# OPTIC.net
KiCad netlist of a schematic drawn in Altium Designer
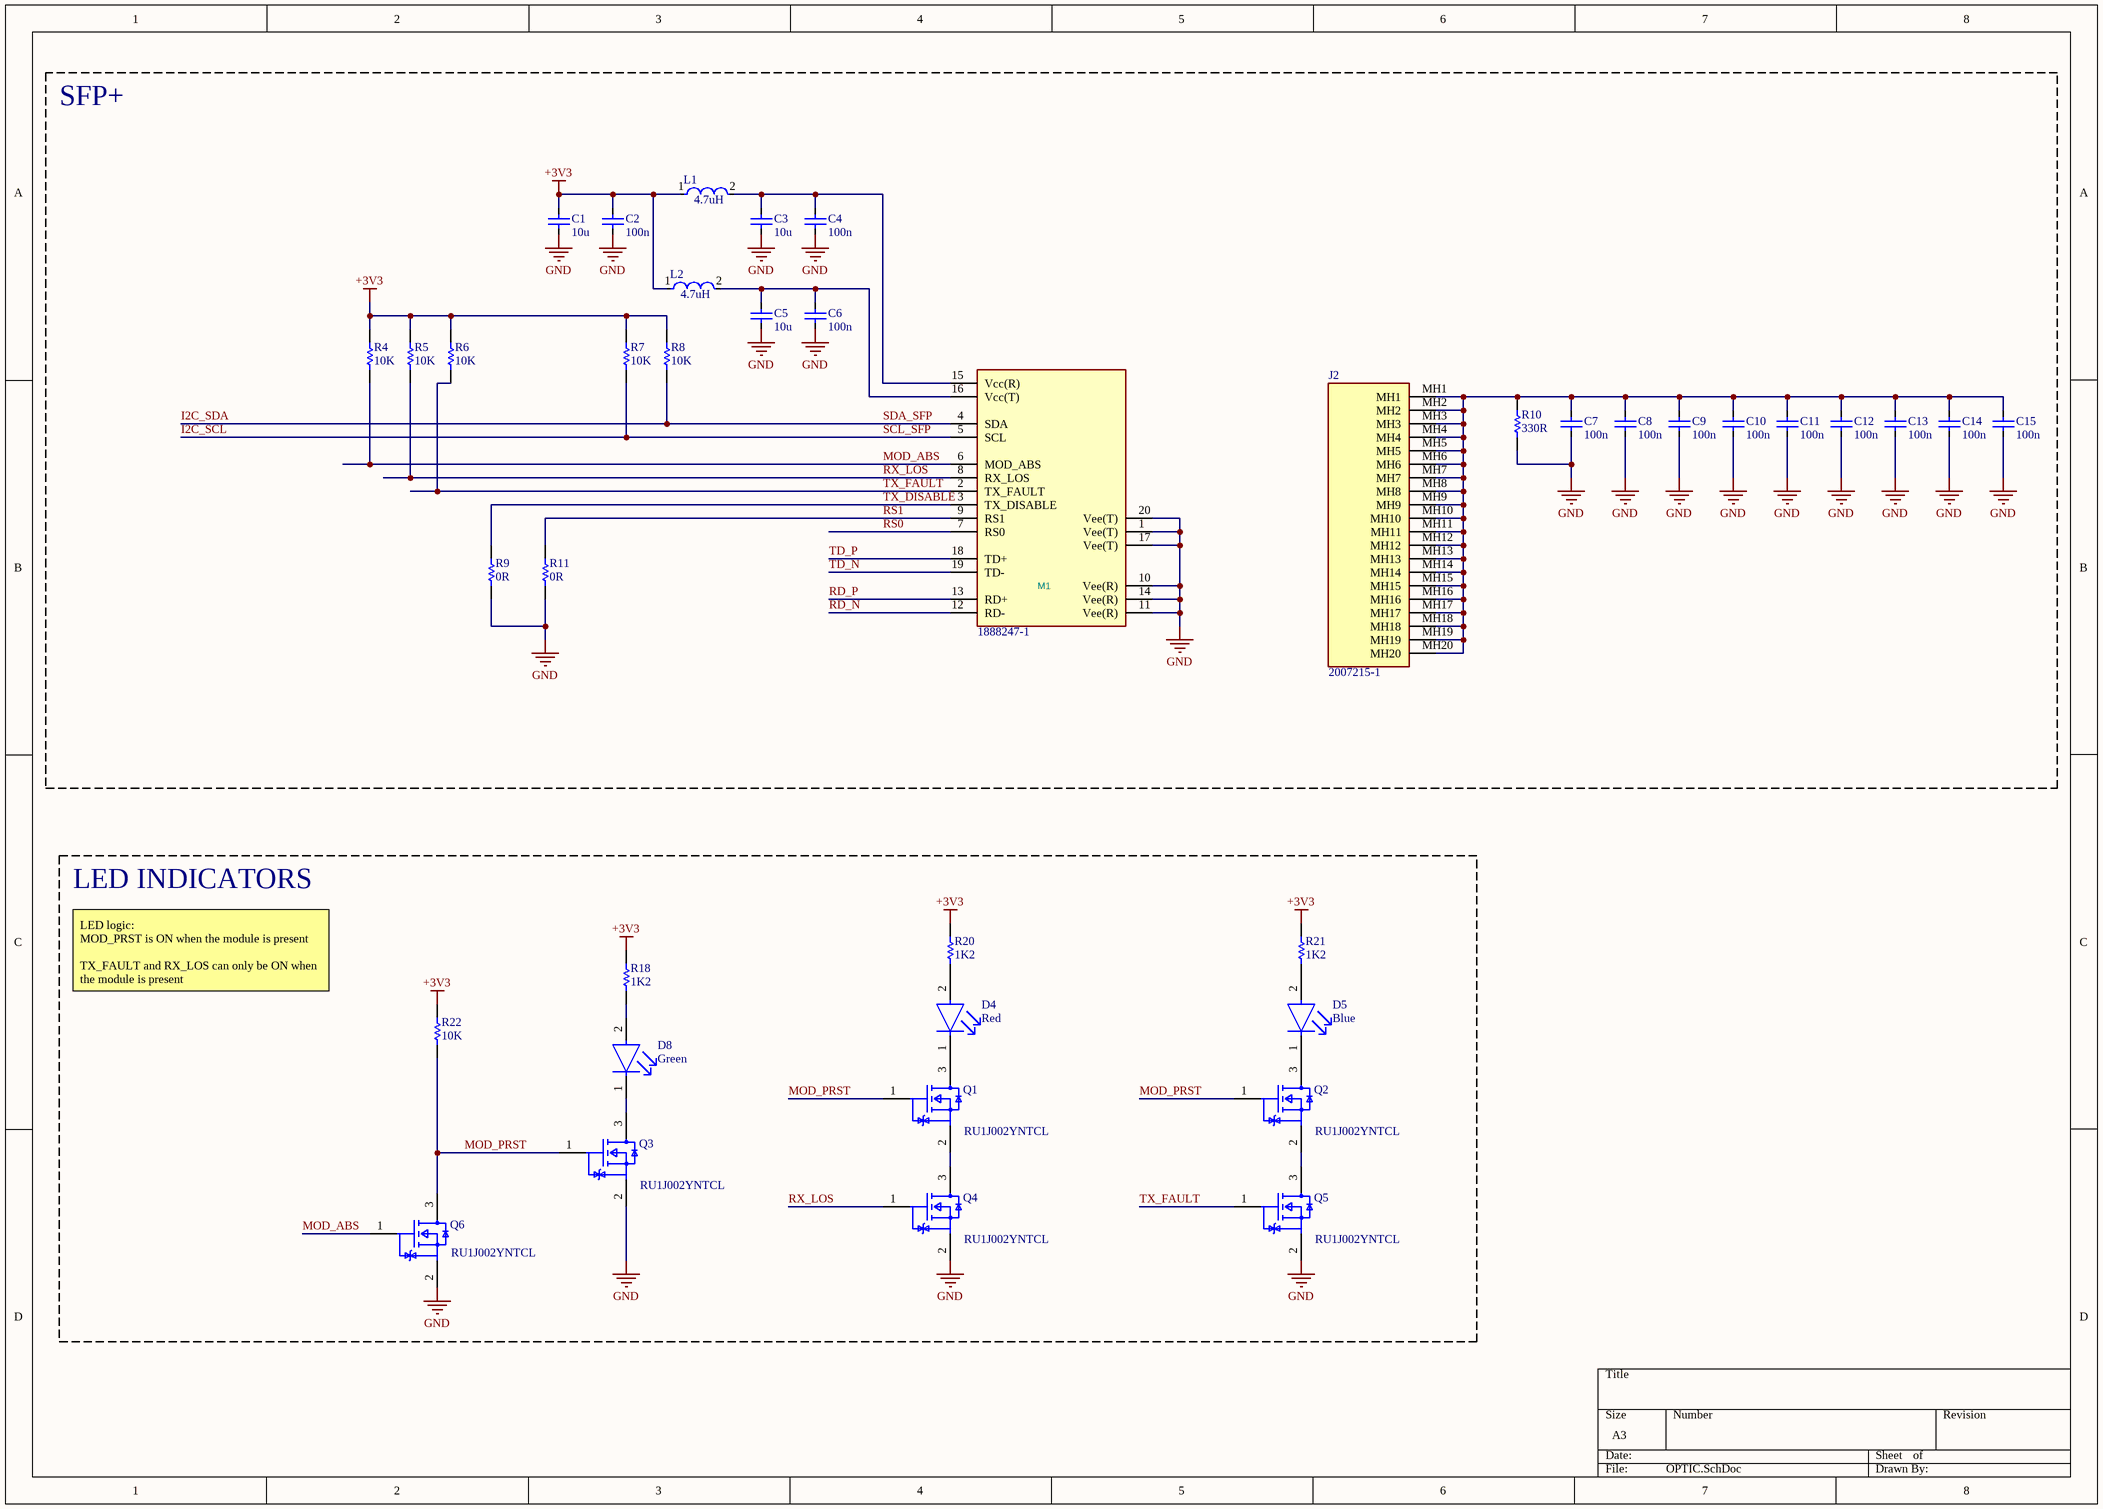
[diagram p0: OPTIC.SchDoc]

(export (version "E")
  (design (tool "Eeschema 10.0.6"))
  (components
    (comp (ref "C1")
      (value "10u")
      (footprint "FP-C1608-080-0_1-IPC_C")
      (description "MLCC 10μF ±10% 6.3V JB SMD 0603")
      (fields (field (name "TOLERANCE") "10%") (field (name "Comment") "C1608JB0J106K080AB"))
      (libsource (lib "Schlib1") (part "C1608JB0J106K080AB"))
    )
    (comp (ref "C2")
      (value "100n")
      (footprint "FP-C1005-050-0_05-IPC_C")
      (description "MLCC 100nF ±10% 50V X7R SMD 0402")
      (fields (field (name "VOLTAGE") "50V") (field (name "TOLERANCE") "10%"))
      (libsource (lib "Schlib1") (part "C1005X7R1H104K050BB"))
    )
    (comp (ref "C3")
      (value "10u")
      (footprint "FP-C1608-080-0_1-IPC_C")
      (description "MLCC 10μF ±10% 6.3V JB SMD 0603")
      (fields (field (name "TOLERANCE") "10%") (field (name "Comment") "C1608JB0J106K080AB"))
      (libsource (lib "Schlib1") (part "C1608JB0J106K080AB"))
    )
    (comp (ref "C4")
      (value "100n")
      (footprint "FP-C1005-050-0_05-IPC_C")
      (description "MLCC 100nF ±10% 50V X7R SMD 0402")
      (fields (field (name "VOLTAGE") "50V") (field (name "TOLERANCE") "10%"))
      (libsource (lib "Schlib1") (part "C1005X7R1H104K050BB"))
    )
    (comp (ref "C5")
      (value "10u")
      (footprint "FP-C1608-080-0_1-IPC_C")
      (description "MLCC 10μF ±10% 6.3V JB SMD 0603")
      (fields (field (name "TOLERANCE") "10%") (field (name "Comment") "C1608JB0J106K080AB"))
      (libsource (lib "Schlib1") (part "C1608JB0J106K080AB"))
    )
    (comp (ref "C6")
      (value "100n")
      (footprint "FP-C1005-050-0_05-IPC_C")
      (description "MLCC 100nF ±10% 50V X7R SMD 0402")
      (fields (field (name "VOLTAGE") "50V") (field (name "TOLERANCE") "10%"))
      (libsource (lib "Schlib1") (part "C1005X7R1H104K050BB"))
    )
    (comp (ref "C7")
      (value "100n")
      (footprint "FP-C1005-050-0_05-IPC_C")
      (description "MLCC 100nF ±10% 50V X7R SMD 0402")
      (fields (field (name "VOLTAGE") "50V") (field (name "TOLERANCE") "10%"))
      (libsource (lib "Schlib1") (part "C1005X7R1H104K050BB"))
    )
    (comp (ref "C8")
      (value "100n")
      (footprint "FP-C1005-050-0_05-IPC_C")
      (description "MLCC 100nF ±10% 50V X7R SMD 0402")
      (fields (field (name "VOLTAGE") "50V") (field (name "TOLERANCE") "10%"))
      (libsource (lib "Schlib1") (part "C1005X7R1H104K050BB"))
    )
    (comp (ref "C9")
      (value "100n")
      (footprint "FP-C1005-050-0_05-IPC_C")
      (description "MLCC 100nF ±10% 50V X7R SMD 0402")
      (fields (field (name "VOLTAGE") "50V") (field (name "TOLERANCE") "10%"))
      (libsource (lib "Schlib1") (part "C1005X7R1H104K050BB"))
    )
    (comp (ref "C10")
      (value "100n")
      (footprint "FP-C1005-050-0_05-IPC_C")
      (description "MLCC 100nF ±10% 50V X7R SMD 0402")
      (fields (field (name "VOLTAGE") "50V") (field (name "TOLERANCE") "10%"))
      (libsource (lib "Schlib1") (part "C1005X7R1H104K050BB"))
    )
    (comp (ref "C11")
      (value "100n")
      (footprint "FP-C1005-050-0_05-IPC_C")
      (description "MLCC 100nF ±10% 50V X7R SMD 0402")
      (fields (field (name "VOLTAGE") "50V") (field (name "TOLERANCE") "10%"))
      (libsource (lib "Schlib1") (part "C1005X7R1H104K050BB"))
    )
    (comp (ref "C12")
      (value "100n")
      (footprint "FP-C1005-050-0_05-IPC_C")
      (description "MLCC 100nF ±10% 50V X7R SMD 0402")
      (fields (field (name "VOLTAGE") "50V") (field (name "TOLERANCE") "10%"))
      (libsource (lib "Schlib1") (part "C1005X7R1H104K050BB"))
    )
    (comp (ref "C13")
      (value "100n")
      (footprint "FP-C1005-050-0_05-IPC_C")
      (description "MLCC 100nF ±10% 50V X7R SMD 0402")
      (fields (field (name "VOLTAGE") "50V") (field (name "TOLERANCE") "10%"))
      (libsource (lib "Schlib1") (part "C1005X7R1H104K050BB"))
    )
    (comp (ref "C14")
      (value "100n")
      (footprint "FP-C1005-050-0_05-IPC_C")
      (description "MLCC 100nF ±10% 50V X7R SMD 0402")
      (fields (field (name "VOLTAGE") "50V") (field (name "TOLERANCE") "10%"))
      (libsource (lib "Schlib1") (part "C1005X7R1H104K050BB"))
    )
    (comp (ref "C15")
      (value "100n")
      (footprint "FP-C1005-050-0_05-IPC_C")
      (description "MLCC 100nF ±10% 50V X7R SMD 0402")
      (fields (field (name "VOLTAGE") "50V") (field (name "TOLERANCE") "10%"))
      (libsource (lib "Schlib1") (part "C1005X7R1H104K050BB"))
    )
    (comp (ref "D4")
      (value "LTST-C191KRKT")
      (footprint "FP-LTST-C191KRKT-MFG")
      (fields (field (name "VOLTAGE") "2V") (field (name "COLOR") "Red"))
      (libsource (lib "Altium Content Vault") (part "8706943c75ba83719d021d2fdc84c58"))
    )
    (comp (ref "D5")
      (value "LTST-C191TBKT")
      (footprint "FP-LTST-C191TBKT-MFG")
      (description "LED BLUE CLEAR CHIP SMD")
      (fields (field (name "COLOR") "Blue"))
      (libsource (lib "Altium Content Vault") (part "8706943c75ba83719d021d2fdc84c58"))
    )
    (comp (ref "D8")
      (value "LTST-C191GKT")
      (footprint "FP-LTST-C191GKT-MFG")
      (description "LED GREEN CLEAR CHIP SMD")
      (fields (field (name "COLOR") "Green"))
      (libsource (lib "Altium Content Vault") (part "8706943c75ba83719d021d2fdc84c58"))
    )
    (comp (ref "J2")
      (value "2007215-1")
      (footprint "2007215-1")
      (description "Position SFP+ Cage Connector Press-Fit Through Hole")
      (libsource (lib "Schlib1") (part "2007215-1"))
    )
    (comp (ref "L1")
      (value "DFE252012P-4R7M=P2")
      (footprint "FP-DFE252012C-IPC_C")
      (description "Shielded Wirewound Inductor 4.7uH 20% 1400mA 0.2Ω 1008 (2520)")
      (fields (field (name "INDUCTANCE") "4.7uH") (field (name "TOLERANCE") "20%"))
      (libsource (lib "Altium Content Vault") (part "725321dda6339637d4d059423bc1c3c"))
    )
    (comp (ref "L2")
      (value "DFE252012P-4R7M=P2")
      (footprint "FP-DFE252012C-IPC_C")
      (description "Shielded Wirewound Inductor 4.7uH 20% 1400mA 0.2Ω 1008 (2520)")
      (fields (field (name "INDUCTANCE") "4.7uH") (field (name "TOLERANCE") "20%"))
      (libsource (lib "Altium Content Vault") (part "725321dda6339637d4d059423bc1c3c"))
    )
    (comp (ref "M1")
      (value "1888247-1")
      (footprint "1888247-1")
      (fields (field (name "MANUFACTURER") "TE Connectivity (TE") (field (name "AUTHOR") "Parsa Malekpor"))
      (libsource (lib "Schlib1") (part "1888247-1"))
    )
    (comp (ref "Q1")
      (value "RU1J002YNTCL")
      (footprint "FP-UMT3F-MFG")
      (description "MOSFET N-CH 50V 0.2A UMT3F")
      (fields
        (field (name "MANUFACTURER") "Rohm")
        (field (name "OCTOPART") "https://octopart.com/ru1j002yntcl-rohm-47197697")
      )
      (libsource (lib "Schlib1") (part "RU1J002YNTCL"))
    )
    (comp (ref "Q2")
      (value "RU1J002YNTCL")
      (footprint "FP-UMT3F-MFG")
      (description "MOSFET N-CH 50V 0.2A UMT3F")
      (fields
        (field (name "MANUFACTURER") "Rohm")
        (field (name "OCTOPART") "https://octopart.com/ru1j002yntcl-rohm-47197697")
      )
      (libsource (lib "Schlib1") (part "RU1J002YNTCL"))
    )
    (comp (ref "Q3")
      (value "RU1J002YNTCL")
      (footprint "FP-UMT3F-MFG")
      (description "MOSFET N-CH 50V 0.2A UMT3F")
      (fields
        (field (name "MANUFACTURER") "Rohm")
        (field (name "OCTOPART") "https://octopart.com/ru1j002yntcl-rohm-47197697")
      )
      (libsource (lib "Schlib1") (part "RU1J002YNTCL"))
    )
    (comp (ref "Q4")
      (value "RU1J002YNTCL")
      (footprint "FP-UMT3F-MFG")
      (description "MOSFET N-CH 50V 0.2A UMT3F")
      (fields
        (field (name "MANUFACTURER") "Rohm")
        (field (name "OCTOPART") "https://octopart.com/ru1j002yntcl-rohm-47197697")
      )
      (libsource (lib "Schlib1") (part "RU1J002YNTCL"))
    )
    (comp (ref "Q5")
      (value "RU1J002YNTCL")
      (footprint "FP-UMT3F-MFG")
      (description "MOSFET N-CH 50V 0.2A UMT3F")
      (fields
        (field (name "MANUFACTURER") "Rohm")
        (field (name "OCTOPART") "https://octopart.com/ru1j002yntcl-rohm-47197697")
      )
      (libsource (lib "Schlib1") (part "RU1J002YNTCL"))
    )
    (comp (ref "Q6")
      (value "RU1J002YNTCL")
      (footprint "FP-UMT3F-MFG")
      (description "MOSFET N-CH 50V 0.2A UMT3F")
      (fields
        (field (name "MANUFACTURER") "Rohm")
        (field (name "OCTOPART") "https://octopart.com/ru1j002yntcl-rohm-47197697")
      )
      (libsource (lib "Schlib1") (part "RU1J002YNTCL"))
    )
    (comp (ref "R4")
      (value "10K")
      (footprint "RESC1005X40X25LL05T10")
      (fields (field (name "PART NUMBER") "RC0402FR-0710KL") (field (name "MANUFACTURER") "Yageo / Phycomp"))
      (libsource (lib "Altium Content Vault") (part "RES"))
    )
    (comp (ref "R5")
      (value "10K")
      (footprint "RESC1005X40X25LL05T10")
      (fields (field (name "PART NUMBER") "RC0402FR-0710KL") (field (name "MANUFACTURER") "Yageo / Phycomp"))
      (libsource (lib "Altium Content Vault") (part "RES"))
    )
    (comp (ref "R6")
      (value "10K")
      (footprint "RESC1005X40X25LL05T10")
      (fields (field (name "PART NUMBER") "RC0402FR-0710KL") (field (name "MANUFACTURER") "Yageo / Phycomp"))
      (libsource (lib "Altium Content Vault") (part "RES"))
    )
    (comp (ref "R7")
      (value "10K")
      (footprint "RESC1005X40X25LL05T10")
      (fields (field (name "PART NUMBER") "RC0402FR-0710KL") (field (name "MANUFACTURER") "Yageo / Phycomp"))
      (libsource (lib "Altium Content Vault") (part "RES"))
    )
    (comp (ref "R8")
      (value "10K")
      (footprint "RESC1005X40X25LL05T10")
      (fields (field (name "PART NUMBER") "RC0402FR-0710KL") (field (name "MANUFACTURER") "Yageo / Phycomp"))
      (libsource (lib "Altium Content Vault") (part "RES"))
    )
    (comp (ref "R9")
      (value "0R")
      (footprint "RESC1005X40X25LL05T10")
      (fields (field (name "PART NUMBER") "RC0402FR-070RL") (field (name "MANUFACTURER") "Yageo / Phycomp"))
      (libsource (lib "Altium Content Vault") (part "RES"))
    )
    (comp (ref "R10")
      (value "330R")
      (footprint "RESC1005X40X25LL05T10")
      (fields (field (name "PART NUMBER") "RC0402FR-07330RL") (field (name "MANUFACTURER") "Yageo / Phycomp"))
      (libsource (lib "Altium Content Vault") (part "RES"))
    )
    (comp (ref "R11")
      (value "0R")
      (footprint "RESC1005X40X25LL05T10")
      (fields (field (name "PART NUMBER") "RC0402FR-070RL") (field (name "MANUFACTURER") "Yageo / Phycomp"))
      (libsource (lib "Altium Content Vault") (part "RES"))
    )
    (comp (ref "R18")
      (value "1K2")
      (footprint "RESC1005X40X25ML05T10")
      (fields (field (name "PART NUMBER") "RC0402FR-071K2L") (field (name "MANUFACTURER") "Yageo / Phycomp"))
      (libsource (lib "Altium Content Vault") (part "RES"))
    )
    (comp (ref "R20")
      (value "1K2")
      (footprint "RESC1005X40X25ML05T10")
      (fields (field (name "PART NUMBER") "RC0402FR-071K2L") (field (name "MANUFACTURER") "Yageo / Phycomp"))
      (libsource (lib "Altium Content Vault") (part "RES"))
    )
    (comp (ref "R21")
      (value "1K2")
      (footprint "RESC1005X40X25ML05T10")
      (fields (field (name "PART NUMBER") "RC0402FR-071K2L") (field (name "MANUFACTURER") "Yageo / Phycomp"))
      (libsource (lib "Altium Content Vault") (part "RES"))
    )
    (comp (ref "R22")
      (value "10K")
      (footprint "RESC1005X40X25LL05T10")
      (fields (field (name "PART NUMBER") "RC0402FR-0710KL") (field (name "MANUFACTURER") "Yageo / Phycomp"))
      (libsource (lib "Altium Content Vault") (part "RES"))
    )
  )
  (nets
    (net (code "1") (name "+3V3") (class "Default")
      (node (ref "C1") (pin "1") (pinfunction "1_1") (pintype "passive"))
      (node (ref "C2") (pin "1") (pinfunction "1_1") (pintype "passive"))
      (node (ref "L1") (pin "1") (pinfunction "1_1") (pintype "passive"))
      (node (ref "L2") (pin "1") (pinfunction "1_1") (pintype "passive"))
      (node (ref "R18") (pin "1") (pinfunction "1_1") (pintype "passive"))
      (node (ref "R20") (pin "1") (pinfunction "1_1") (pintype "passive"))
      (node (ref "R21") (pin "1") (pinfunction "1_1") (pintype "passive"))
      (node (ref "R22") (pin "1") (pinfunction "1_1") (pintype "passive"))
      (node (ref "R4") (pin "1") (pinfunction "1_1") (pintype "passive"))
      (node (ref "R5") (pin "1") (pinfunction "1_1") (pintype "passive"))
      (node (ref "R6") (pin "1") (pinfunction "1_1") (pintype "passive"))
      (node (ref "R7") (pin "1") (pinfunction "1_1") (pintype "passive"))
      (node (ref "R8") (pin "1") (pinfunction "1_1") (pintype "passive"))
    )
    (net (code "2") (name "/I2C_SCL") (class "Default")
      (node (ref "M1") (pin "5") (pinfunction "SCL_5") (pintype "passive"))
      (node (ref "R7") (pin "2") (pinfunction "2_2") (pintype "passive"))
    )
    (net (code "3") (name "/I2C_SDA") (class "Default")
      (node (ref "M1") (pin "4") (pinfunction "SDA_4") (pintype "passive"))
      (node (ref "R8") (pin "2") (pinfunction "2_2") (pintype "passive"))
    )
    (net (code "4") (name "/MOD_ABS") (class "Default")
      (node (ref "M1") (pin "6") (pinfunction "MOD_ABS_6") (pintype "passive"))
      (node (ref "Q6") (pin "1") (pinfunction "G_1") (pintype "passive"))
      (node (ref "R4") (pin "2") (pinfunction "2_2") (pintype "passive"))
    )
    (net (code "5") (name "/MOD_PRST") (class "Default")
      (node (ref "Q1") (pin "1") (pinfunction "G_1") (pintype "passive"))
      (node (ref "Q2") (pin "1") (pinfunction "G_1") (pintype "passive"))
      (node (ref "Q3") (pin "1") (pinfunction "G_1") (pintype "passive"))
      (node (ref "Q6") (pin "3") (pinfunction "D_3") (pintype "passive"))
      (node (ref "R22") (pin "2") (pinfunction "2_2") (pintype "passive"))
    )
    (net (code "6") (name "/RD_N") (class "Default")
      (node (ref "M1") (pin "12") (pinfunction "RD-_12") (pintype "passive"))
    )
    (net (code "7") (name "/RD_P") (class "Default")
      (node (ref "M1") (pin "13") (pinfunction "RD+_13") (pintype "passive"))
    )
    (net (code "8") (name "/RS0") (class "Default")
      (node (ref "M1") (pin "7") (pinfunction "RS0_7") (pintype "passive"))
    )
    (net (code "9") (name "/RS1") (class "Default")
      (node (ref "M1") (pin "9") (pinfunction "RS1_9") (pintype "passive"))
      (node (ref "R11") (pin "1") (pinfunction "1_1") (pintype "passive"))
    )
    (net (code "10") (name "/RX_LOS") (class "Default")
      (node (ref "M1") (pin "8") (pinfunction "RX_LOS_8") (pintype "passive"))
      (node (ref "Q4") (pin "1") (pinfunction "G_1") (pintype "passive"))
      (node (ref "R5") (pin "2") (pinfunction "2_2") (pintype "passive"))
    )
    (net (code "11") (name "/TD_N") (class "Default")
      (node (ref "M1") (pin "19") (pinfunction "TD-_19") (pintype "passive"))
    )
    (net (code "12") (name "/TD_P") (class "Default")
      (node (ref "M1") (pin "18") (pinfunction "TD+_18") (pintype "passive"))
    )
    (net (code "13") (name "/TX_DISABLE") (class "Default")
      (node (ref "M1") (pin "3") (pinfunction "TX_DISABLE_3") (pintype "passive"))
      (node (ref "R9") (pin "1") (pinfunction "1_1") (pintype "passive"))
    )
    (net (code "14") (name "/TX_FAULT") (class "Default")
      (node (ref "M1") (pin "2") (pinfunction "TX_FAULT_2") (pintype "passive"))
      (node (ref "Q5") (pin "1") (pinfunction "G_1") (pintype "passive"))
      (node (ref "R6") (pin "2") (pinfunction "2_2") (pintype "passive"))
    )
    (net (code "15") (name "GND") (class "Default")
      (node (ref "C1") (pin "2") (pinfunction "2_2") (pintype "passive"))
      (node (ref "C10") (pin "2") (pinfunction "2_2") (pintype "passive"))
      (node (ref "C11") (pin "2") (pinfunction "2_2") (pintype "passive"))
      (node (ref "C12") (pin "2") (pinfunction "2_2") (pintype "passive"))
      (node (ref "C13") (pin "2") (pinfunction "2_2") (pintype "passive"))
      (node (ref "C14") (pin "2") (pinfunction "2_2") (pintype "passive"))
      (node (ref "C15") (pin "2") (pinfunction "2_2") (pintype "passive"))
      (node (ref "C2") (pin "2") (pinfunction "2_2") (pintype "passive"))
      (node (ref "C3") (pin "2") (pinfunction "2_2") (pintype "passive"))
      (node (ref "C4") (pin "2") (pinfunction "2_2") (pintype "passive"))
      (node (ref "C5") (pin "2") (pinfunction "2_2") (pintype "passive"))
      (node (ref "C6") (pin "2") (pinfunction "2_2") (pintype "passive"))
      (node (ref "C7") (pin "2") (pinfunction "2_2") (pintype "passive"))
      (node (ref "C8") (pin "2") (pinfunction "2_2") (pintype "passive"))
      (node (ref "C9") (pin "2") (pinfunction "2_2") (pintype "passive"))
      (node (ref "M1") (pin "1") (pinfunction "Vee(T)_1") (pintype "passive"))
      (node (ref "M1") (pin "10") (pinfunction "Vee(R)_10") (pintype "passive"))
      (node (ref "M1") (pin "11") (pinfunction "Vee(R)_11") (pintype "passive"))
      (node (ref "M1") (pin "14") (pinfunction "Vee(R)_14") (pintype "passive"))
      (node (ref "M1") (pin "17") (pinfunction "Vee(T)_17") (pintype "passive"))
      (node (ref "M1") (pin "20") (pinfunction "Vee(T)_20") (pintype "passive"))
      (node (ref "Q3") (pin "2") (pinfunction "S_2") (pintype "passive"))
      (node (ref "Q4") (pin "2") (pinfunction "S_2") (pintype "passive"))
      (node (ref "Q5") (pin "2") (pinfunction "S_2") (pintype "passive"))
      (node (ref "Q6") (pin "2") (pinfunction "S_2") (pintype "passive"))
      (node (ref "R10") (pin "2") (pinfunction "2_2") (pintype "passive"))
      (node (ref "R11") (pin "2") (pinfunction "2_2") (pintype "passive"))
      (node (ref "R9") (pin "2") (pinfunction "2_2") (pintype "passive"))
    )
    (net (code "16") (name "Net-(C10-Pad1)") (class "Default")
      (node (ref "C10") (pin "1") (pinfunction "1_1") (pintype "passive"))
      (node (ref "C11") (pin "1") (pinfunction "1_1") (pintype "passive"))
      (node (ref "C12") (pin "1") (pinfunction "1_1") (pintype "passive"))
      (node (ref "C13") (pin "1") (pinfunction "1_1") (pintype "passive"))
      (node (ref "C14") (pin "1") (pinfunction "1_1") (pintype "passive"))
      (node (ref "C15") (pin "1") (pinfunction "1_1") (pintype "passive"))
      (node (ref "C7") (pin "1") (pinfunction "1_1") (pintype "passive"))
      (node (ref "C8") (pin "1") (pinfunction "1_1") (pintype "passive"))
      (node (ref "C9") (pin "1") (pinfunction "1_1") (pintype "passive"))
      (node (ref "J2") (pin "MH1") (pinfunction "MH1_MH1") (pintype "passive"))
      (node (ref "J2") (pin "MH10") (pinfunction "MH10_MH10") (pintype "passive"))
      (node (ref "J2") (pin "MH11") (pinfunction "MH11_MH11") (pintype "passive"))
      (node (ref "J2") (pin "MH12") (pinfunction "MH12_MH12") (pintype "passive"))
      (node (ref "J2") (pin "MH13") (pinfunction "MH13_MH13") (pintype "passive"))
      (node (ref "J2") (pin "MH14") (pinfunction "MH14_MH14") (pintype "passive"))
      (node (ref "J2") (pin "MH15") (pinfunction "MH15_MH15") (pintype "passive"))
      (node (ref "J2") (pin "MH16") (pinfunction "MH16_MH16") (pintype "passive"))
      (node (ref "J2") (pin "MH17") (pinfunction "MH17_MH17") (pintype "passive"))
      (node (ref "J2") (pin "MH18") (pinfunction "MH18_MH18") (pintype "passive"))
      (node (ref "J2") (pin "MH19") (pinfunction "MH19_MH19") (pintype "passive"))
      (node (ref "J2") (pin "MH2") (pinfunction "MH2_MH2") (pintype "passive"))
      (node (ref "J2") (pin "MH20") (pinfunction "MH20_MH20") (pintype "passive"))
      (node (ref "J2") (pin "MH3") (pinfunction "MH3_MH3") (pintype "passive"))
      (node (ref "J2") (pin "MH4") (pinfunction "MH4_MH4") (pintype "passive"))
      (node (ref "J2") (pin "MH5") (pinfunction "MH5_MH5") (pintype "passive"))
      (node (ref "J2") (pin "MH6") (pinfunction "MH6_MH6") (pintype "passive"))
      (node (ref "J2") (pin "MH7") (pinfunction "MH7_MH7") (pintype "passive"))
      (node (ref "J2") (pin "MH8") (pinfunction "MH8_MH8") (pintype "passive"))
      (node (ref "J2") (pin "MH9") (pinfunction "MH9_MH9") (pintype "passive"))
      (node (ref "R10") (pin "1") (pinfunction "1_1") (pintype "passive"))
    )
    (net (code "17") (name "Net-(D4-A)") (class "Default")
      (node (ref "D4") (pin "2") (pinfunction "A_2") (pintype "passive"))
      (node (ref "R20") (pin "2") (pinfunction "2_2") (pintype "passive"))
    )
    (net (code "18") (name "Net-(D4-C)") (class "Default")
      (node (ref "D4") (pin "1") (pinfunction "C_1") (pintype "passive"))
      (node (ref "Q1") (pin "3") (pinfunction "D_3") (pintype "passive"))
    )
    (net (code "19") (name "Net-(D5-A)") (class "Default")
      (node (ref "D5") (pin "2") (pinfunction "A_2") (pintype "passive"))
      (node (ref "R21") (pin "2") (pinfunction "2_2") (pintype "passive"))
    )
    (net (code "20") (name "Net-(D5-C)") (class "Default")
      (node (ref "D5") (pin "1") (pinfunction "C_1") (pintype "passive"))
      (node (ref "Q2") (pin "3") (pinfunction "D_3") (pintype "passive"))
    )
    (net (code "21") (name "Net-(D8-A)") (class "Default")
      (node (ref "D8") (pin "2") (pinfunction "A_2") (pintype "passive"))
      (node (ref "R18") (pin "2") (pinfunction "2_2") (pintype "passive"))
    )
    (net (code "22") (name "Net-(D8-C)") (class "Default")
      (node (ref "D8") (pin "1") (pinfunction "C_1") (pintype "passive"))
      (node (ref "Q3") (pin "3") (pinfunction "D_3") (pintype "passive"))
    )
    (net (code "23") (name "Net-(M1-Vcc(R))") (class "Default")
      (node (ref "C3") (pin "1") (pinfunction "1_1") (pintype "passive"))
      (node (ref "C4") (pin "1") (pinfunction "1_1") (pintype "passive"))
      (node (ref "L1") (pin "2") (pinfunction "2_2") (pintype "passive"))
      (node (ref "M1") (pin "15") (pinfunction "Vcc(R)_15") (pintype "passive"))
    )
    (net (code "24") (name "Net-(M1-Vcc(T))") (class "Default")
      (node (ref "C5") (pin "1") (pinfunction "1_1") (pintype "passive"))
      (node (ref "C6") (pin "1") (pinfunction "1_1") (pintype "passive"))
      (node (ref "L2") (pin "2") (pinfunction "2_2") (pintype "passive"))
      (node (ref "M1") (pin "16") (pinfunction "Vcc(T)_16") (pintype "passive"))
    )
    (net (code "25") (name "Net-(Q1-S)") (class "Default")
      (node (ref "Q1") (pin "2") (pinfunction "S_2") (pintype "passive"))
      (node (ref "Q4") (pin "3") (pinfunction "D_3") (pintype "passive"))
    )
    (net (code "26") (name "Net-(Q2-S)") (class "Default")
      (node (ref "Q2") (pin "2") (pinfunction "S_2") (pintype "passive"))
      (node (ref "Q5") (pin "3") (pinfunction "D_3") (pintype "passive"))
    )
  )
)
